# 40-PRE_REG_AND_SERDES_POWER_SUPPLY.net
KiCad netlist of a schematic drawn in Altium Designer
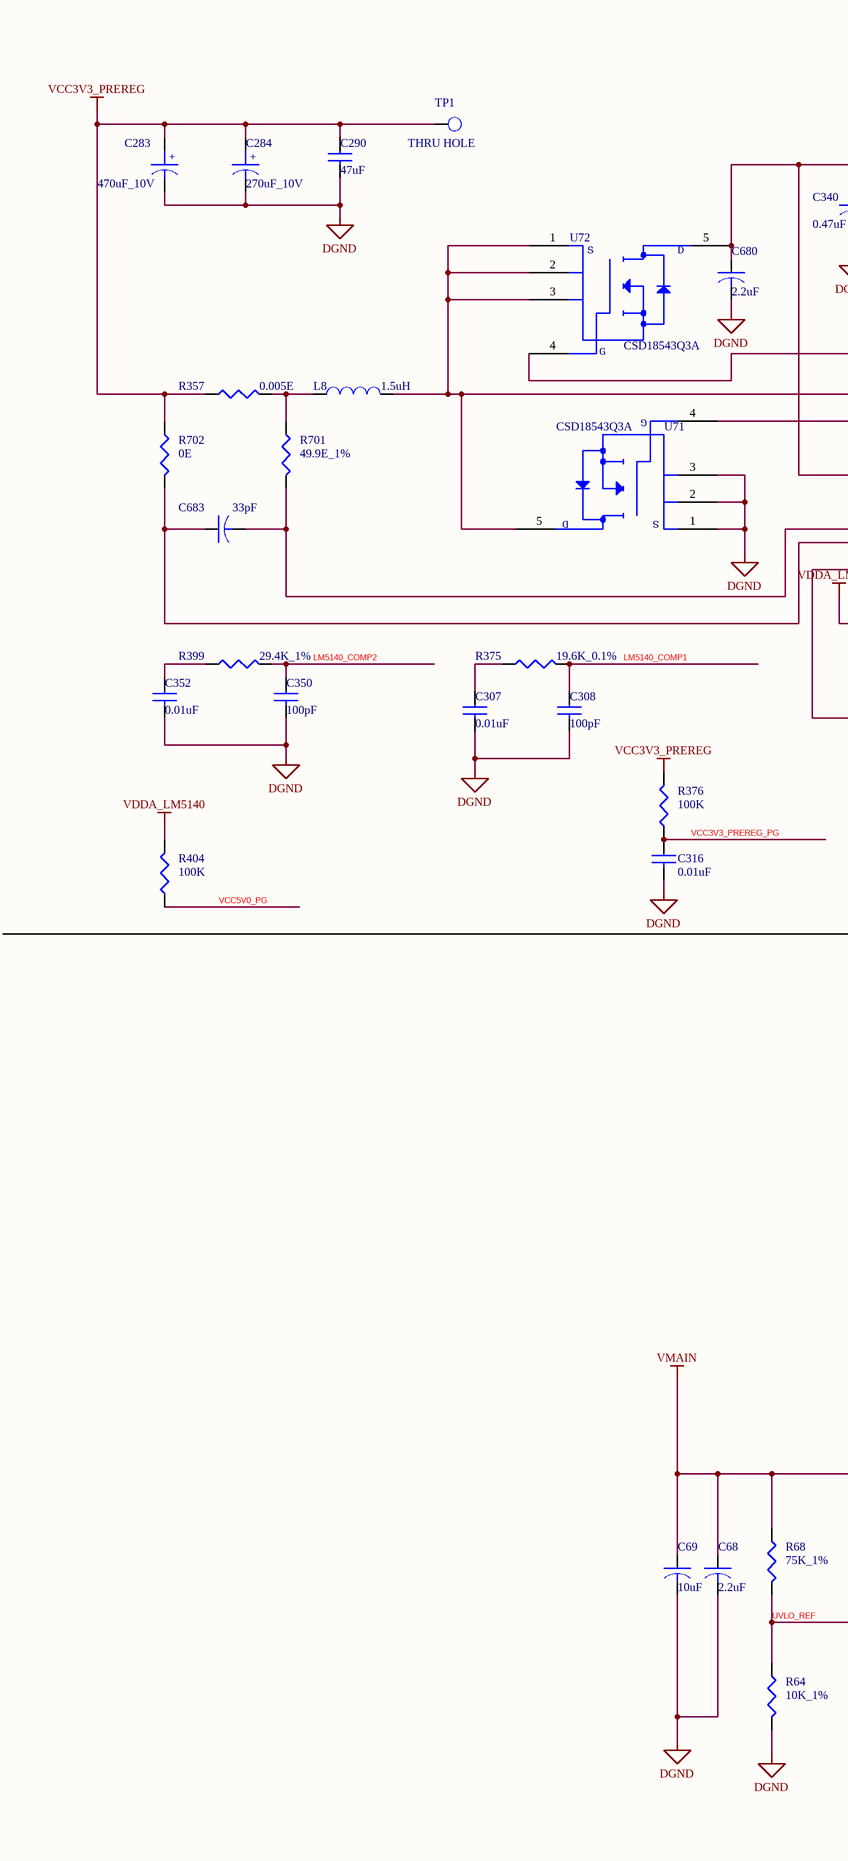
[diagram p0: 40-PRE_REG AND SERDES POWER SUPPLY.SchDoc, left]
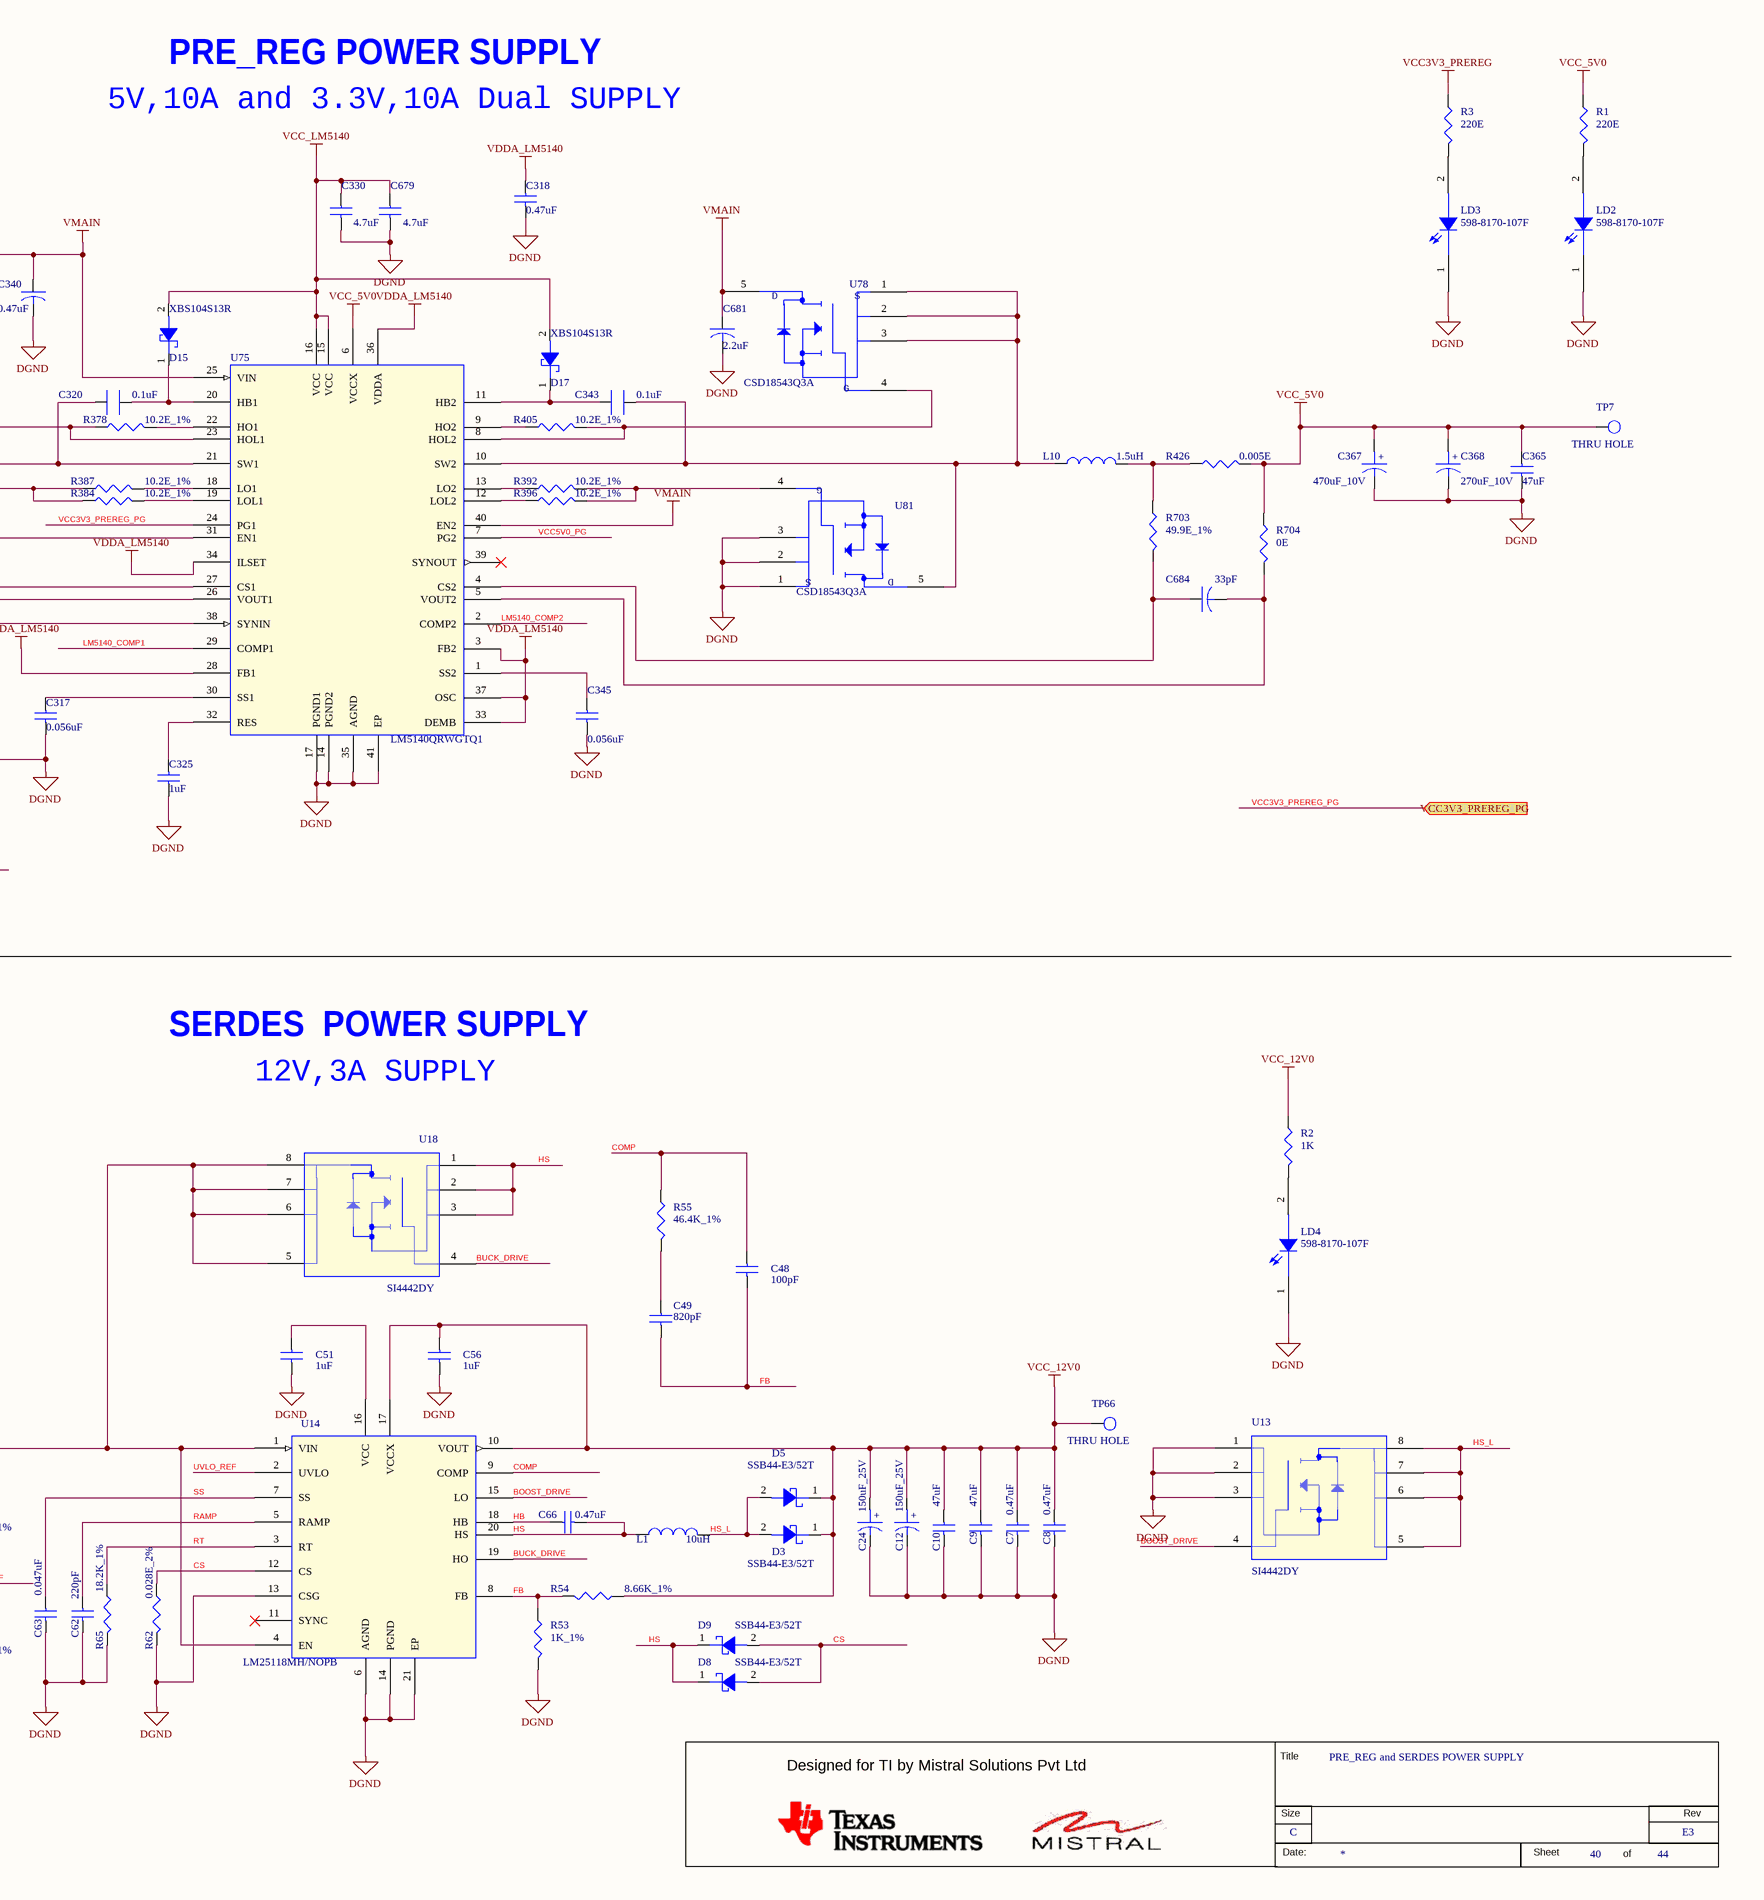
[diagram p1: 40-PRE_REG AND SERDES POWER SUPPLY.SchDoc, right]

(export (version "E")
  (design (tool "Eeschema 10.0.6"))
  (components
    (comp (ref "C7")
      (value "0.47uF")
      (footprint "CAP0805_1")
      (description "CAP CERAMIC 0.47uF 25V 10% X5R 0805")
      (fields (field (name "DISTRIBUTOR_PART_NUMBER") "587-1290-1-ND") (field (name "VOLTAGE") "25V"))
      (libsource (lib "*") (part "CAP_Dup5"))
    )
    (comp (ref "C8")
      (value "0.47uF")
      (footprint "CAP0805_1")
      (description "CAP CERAMIC 0.47uF 25V 10% X5R 0805")
      (fields (field (name "DISTRIBUTOR_PART_NUMBER") "587-1290-1-ND") (field (name "VOLTAGE") "25V"))
      (libsource (lib "*") (part "CAP_Dup5"))
    )
    (comp (ref "C9")
      (value "47uF")
      (footprint "CAP1206_2")
      (description "CAP CERAMIC 47uF 25V 20% X5R 1206")
      (fields (field (name "DISTRIBUTOR_PART_NUMBER") "490-16268-1-ND") (field (name "VOLTAGE") "25V"))
      (libsource (lib "*") (part "CAP_Dup5"))
    )
    (comp (ref "C10")
      (value "47uF")
      (footprint "CAP1206_2")
      (description "CAP CERAMIC 47uF 25V 20% X5R 1206")
      (fields
        (field (name "MISTRAL PART NO") "120013050002-R")
        (field (name "MFR_PART_NUMBER") "GRM31CR61E476ME44L")
      )
      (libsource (lib "*") (part "CAP_Dup5"))
    )
    (comp (ref "C12")
      (value "150uF_25V")
      (footprint "CAPAE_CASE8383_11")
      (description "CAP ELECTROLYTIC 150uF 25V 20% CASE_8383")
      (fields
        (field (name "MISTRAL PART NO") "120018010023-R")
        (field (name "MFR_PART_NUMBER") "UWT1E151MNL1GS")
      )
      (libsource (lib "*") (part "CAP_POL"))
    )
    (comp (ref "C24")
      (value "150uF_25V")
      (footprint "CAPAE_CASE8383_11")
      (description "CAP ELECTROLYTIC 150uF 25V 20% CASE_8383")
      (fields
        (field (name "MISTRAL PART NO") "120018010023-R")
        (field (name "MFR_PART_NUMBER") "UWT1E151MNL1GS")
      )
      (libsource (lib "*") (part "CAP_POL"))
    )
    (comp (ref "C48")
      (value "100pF")
      (footprint "CAP0402")
      (description "CAP CERAMIC 100pF 50V 10% X7R 0402")
      (fields (field (name "DISTRIBUTOR_PART_NUMBER") "311-1419-1-ND") (field (name "VOLTAGE") "50V"))
      (libsource (lib "*") (part "CAP_Dup5"))
    )
    (comp (ref "C49")
      (value "820pF")
      (footprint "CAP0402_0-75")
      (description "CAP CERAMIC 820pF 50V 5% C0G(NP0) 0402")
      (fields (field (name "DISTRIBUTOR_PART_NUMBER") "445-13812-1-ND") (field (name "VOLTAGE") "50V"))
      (libsource (lib "*") (part "CAP_Dup5"))
    )
    (comp (ref "C51")
      (value "1uF")
      (footprint "CAP0603_1")
      (description "CAP CERAMIC 1uF 25V 10% X5R 0603")
      (fields
        (field (name "MISTRAL PART NO") "120010080040-R")
        (field (name "MFR_PART_NUMBER") "06033D105KAT2A")
      )
      (libsource (lib "*") (part "CAP_Dup5"))
    )
    (comp (ref "C56")
      (value "1uF")
      (footprint "CAP0603_1")
      (description "CAP CERAMIC 1uF 25V 10% X5R 0603")
      (fields
        (field (name "MISTRAL PART NO") "120010080040-R")
        (field (name "MFR_PART_NUMBER") "06033D105KAT2A")
      )
      (libsource (lib "*") (part "CAP_Dup5"))
    )
    (comp (ref "C62")
      (value "220pF")
      (footprint "CAP0402")
      (description "CAP CERAMIC 220pF 25V 5% C0G 0402")
      (fields
        (field (name "MISTRAL PART NO") "120015120016-R")
        (field (name "MFR_PART_NUMBER") "GRM1555C1E221JA01D")
      )
      (libsource (lib "*") (part "CAP_Dup5"))
    )
    (comp (ref "C63")
      (value "0.047uF")
      (footprint "CAP0402_0-75")
      (description "CAP CERAMIC 0.047uF 50V 10% X7R 0402")
      (fields (field (name "DISTRIBUTOR_PART_NUMBER") "GRM155R71H473KE14J-ND") (field (name "VOLTAGE") "50V"))
      (libsource (lib "*") (part "CAP_Dup5"))
    )
    (comp (ref "C66")
      (value "0.47uF")
      (footprint "CAP0805_1")
      (description "CAP CERAMIC 0.47uF 25V 10% X5R 0805")
      (fields (field (name "DISTRIBUTOR_PART_NUMBER") "587-1290-1-ND") (field (name "VOLTAGE") "25V"))
      (libsource (lib "*") (part "CAP_Dup5"))
    )
    (comp (ref "C68")
      (value "2.2uF")
      (footprint "CAP0805_1")
      (description "CAP CERAMIC 2.2uF 50V 10% X5R 0805")
      (fields
        (field (name "MISTRAL PART NO") "120018010012-R")
        (field (name "MFR_PART_NUMBER") "C2012X5R1H225K085AB")
      )
      (libsource (lib "*") (part "CAP"))
    )
    (comp (ref "C69")
      (value "10uF")
      (footprint "CAP1206_2")
      (description "CAP CERAMIC 10uF 50V 20% X5R 1206")
      (fields
        (field (name "MISTRAL PART NO") "120018010013-R")
        (field (name "MFR_PART_NUMBER") "GRM31CR61H106MA12L")
      )
      (libsource (lib "*") (part "CAP"))
    )
    (comp (ref "C283")
      (value "470uF_10V")
      (footprint "CAPAE_D8CASE_8")
      (description "CAP ELECTROLYTIC 470uF 10V 20% D8CASE_6666")
      (fields (field (name "DISTRIBUTOR_PART_NUMBER") "P15094CT-ND") (field (name "VOLTAGE") "10V"))
      (libsource (lib "*") (part "CAP_POL"))
    )
    (comp (ref "C284")
      (value "270uF_10V")
      (footprint "CAP_87510524_270X270_SMD_7-7")
      (description "CAP POLMER 270uF 10V 20% SMD")
      (fields
        (field (name "MISTRAL PART NO") "120018010024-R")
        (field (name "MFR_PART_NUMBER") "875105245014")
      )
      (libsource (lib "*") (part "CAP_POL"))
    )
    (comp (ref "C290")
      (value "47uF")
      (footprint "CAP1206_2")
      (description "CAP CERAMIC 47uF 25V 20% X5R 1206")
      (fields
        (field (name "MISTRAL PART NO") "120013050002-R")
        (field (name "MFR_PART_NUMBER") "GRM31CR61E476ME44L")
      )
      (libsource (lib "*") (part "CAP_Dup5"))
    )
    (comp (ref "C307")
      (value "0.01uF")
      (footprint "CAP0402_0-75")
      (description "CAP CERAMIC 0.01uF 10V 10% X7R 0402")
      (fields
        (field (name "MISTRAL PART NO") "120009030017-R")
        (field (name "MFR_PART_NUMBER") "0402ZC103KAT2A")
      )
      (libsource (lib "*") (part "CAP_Dup5"))
    )
    (comp (ref "C308")
      (value "100pF")
      (footprint "CAP0402")
      (description "CAP CERAMIC 100pF 50V 10% X7R 0402")
      (fields
        (field (name "MISTRAL PART NO") "120014030006-R")
        (field (name "MFR_PART_NUMBER") "CC0402KRX7R9BB101")
      )
      (libsource (lib "*") (part "CAP_Dup5"))
    )
    (comp (ref "C316")
      (value "0.01uF")
      (footprint "CAP0201_0-5")
      (description "CAP CERAMIC 0.01uF 25V 10% X5R 0201")
      (fields (field (name "DISTRIBUTOR_PART_NUMBER") "GRM033R61E103KA12J-ND") (field (name "VOLTAGE") "25V"))
      (libsource (lib "*") (part "CAP_Dup5"))
    )
    (comp (ref "C317")
      (value "0.056uF")
      (footprint "CAP0402_0-75")
      (description "CAP CERAMIC 0.056uF 10V 10% X5R 0402")
      (fields (field (name "DISTRIBUTOR_PART_NUMBER") "490-5413-1-ND") (field (name "VOLTAGE") "10V"))
      (libsource (lib "*") (part "CAP_Dup5"))
    )
    (comp (ref "C318")
      (value "0.47uF")
      (footprint "CAP0603_1")
      (description "CAP CERAMIC 0.47uF 25V 10% X7R 0603")
      (fields
        (field (name "MISTRAL PART NO") "120009030111-R")
        (field (name "MFR_PART_NUMBER") "CC0603KRX7R8BB474")
      )
      (libsource (lib "*") (part "CAP_Dup5"))
    )
    (comp (ref "C320")
      (value "0.1uF")
      (footprint "TMDX654GPEVM_BRD:CAP0201_0-5")
      (description "CAP CERAMIC 0.1uF 16V 10% X5R 0201")
      (fields
        (field (name "MISTRAL PART NO") "120009030072-R")
        (field (name "MFR_PART_NUMBER") "GRM033R61C104KE84J")
      )
      (libsource (lib "*") (part "CAP_Dup3"))
    )
    (comp (ref "C325")
      (value "1uF")
      (footprint "CAP0402_0-75")
      (description "CAP CERAMIC 1uF 16V 20% X5R 0402")
      (fields
        (field (name "MISTRAL PART NO") "120018020006-R")
        (field (name "MFR_PART_NUMBER") "EMK105BJ105MV-F")
      )
      (libsource (lib "*") (part "CAP_Dup5"))
    )
    (comp (ref "C330")
      (value "4.7uF")
      (footprint "CAP0402_0-75")
      (description "CAP CERAMIC 4.7uF 10V 20% X5R 0402")
      (fields (field (name "DISTRIBUTOR_PART_NUMBER") "478-10791-1-ND") (field (name "VOLTAGE") "10V"))
      (libsource (lib "*") (part "CAP_Dup5"))
    )
    (comp (ref "C340")
      (value "0.47uF")
      (footprint "CAP0805_1-5")
      (description "CAP CERAMIC 0.47uF 50V 5% X7R 0805")
      (fields
        (field (name "MISTRAL PART NO") "120018010019-R")
        (field (name "MFR_PART_NUMBER") "CC0805JKX7R9BB474")
      )
      (libsource (lib "*") (part "CAP"))
    )
    (comp (ref "C343")
      (value "0.1uF")
      (footprint "TMDX654GPEVM_BRD:CAP0201_0-5")
      (description "CAP CERAMIC 0.1uF 16V 10% X5R 0201")
      (fields (field (name "DISTRIBUTOR_PART_NUMBER") "490-16742-1-ND") (field (name "VOLTAGE") "16V"))
      (libsource (lib "*") (part "CAP_Dup3"))
    )
    (comp (ref "C345")
      (value "0.056uF")
      (footprint "CAP0402_0-75")
      (description "CAP CERAMIC 0.056uF 10V 10% X5R 0402")
      (fields
        (field (name "MISTRAL PART NO") "120018010014-R")
        (field (name "MFR_PART_NUMBER") "GRM155R61A563KA01D")
      )
      (libsource (lib "*") (part "CAP_Dup5"))
    )
    (comp (ref "C350")
      (value "100pF")
      (footprint "CAP0402")
      (description "CAP CERAMIC 100pF 50V 10% X7R 0402")
      (fields (field (name "DISTRIBUTOR_PART_NUMBER") "311-1419-1-ND") (field (name "VOLTAGE") "50V"))
      (libsource (lib "*") (part "CAP_Dup5"))
    )
    (comp (ref "C352")
      (value "0.01uF")
      (footprint "CAP0402_0-75")
      (description "CAP CERAMIC 0.01uF 10V 10% X7R 0402")
      (fields
        (field (name "MISTRAL PART NO") "120009030017-R")
        (field (name "MFR_PART_NUMBER") "0402ZC103KAT2A")
      )
      (libsource (lib "*") (part "CAP_Dup5"))
    )
    (comp (ref "C365")
      (value "47uF")
      (footprint "CAP1206_2")
      (description "CAP CERAMIC 47uF 25V 20% X5R 1206")
      (fields
        (field (name "MISTRAL PART NO") "120013050002-R")
        (field (name "MFR_PART_NUMBER") "GRM31CR61E476ME44L")
      )
      (libsource (lib "*") (part "CAP_Dup5"))
    )
    (comp (ref "C367")
      (value "470uF_10V")
      (footprint "CAPAE_D8CASE_8")
      (description "CAP ELECTROLYTIC 470uF 10V 20% D8CASE_6666")
      (fields (field (name "DISTRIBUTOR_PART_NUMBER") "P15094CT-ND") (field (name "VOLTAGE") "10V"))
      (libsource (lib "*") (part "CAP_POL"))
    )
    (comp (ref "C368")
      (value "270uF_10V")
      (footprint "CAP_87510524_270X270_SMD_7-7")
      (description "CAP POLMER 270uF 10V 20% SMD")
      (fields (field (name "DISTRIBUTOR_PART_NUMBER") "732-6414-1-ND") (field (name "VOLTAGE") "10V"))
      (libsource (lib "*") (part "CAP_POL"))
    )
    (comp (ref "C679")
      (value "4.7uF")
      (footprint "CAP0402_0-75")
      (description "CAP CERAMIC 4.7uF 10V 20% X5R 0402")
      (fields
        (field (name "MISTRAL PART NO") "120012060002-R")
        (field (name "MFR_PART_NUMBER") "0402ZD475MAT2A")
      )
      (libsource (lib "*") (part "CAP_Dup5"))
    )
    (comp (ref "C680")
      (value "2.2uF")
      (footprint "CAP0805_1")
      (description "CAP CERAMIC 2.2uF 50V 10% X5R 0805")
      (fields (field (name "DISTRIBUTOR_PART_NUMBER") "445-14407-1-ND") (field (name "VOLTAGE") "50V"))
      (libsource (lib "*") (part "CAP"))
    )
    (comp (ref "C681")
      (value "2.2uF")
      (footprint "CAP0805_1")
      (description "CAP CERAMIC 2.2uF 50V 10% X5R 0805")
      (fields (field (name "DISTRIBUTOR_PART_NUMBER") "445-14407-1-ND") (field (name "VOLTAGE") "50V"))
      (libsource (lib "*") (part "CAP"))
    )
    (comp (ref "C683")
      (value "33pF")
      (footprint "CAP0201_0-5")
      (description "CAP CERAMIC 33pF 50V 2% C0G(NP0) 0201")
      (fields
        (field (name "MISTRAL PART NO") "120018010015-R")
        (field (name "MFR_PART_NUMBER") "GRM0335C1H330GA01D")
      )
      (libsource (lib "*") (part "CAP"))
    )
    (comp (ref "C684")
      (value "33pF")
      (footprint "CAP0201_0-5")
      (description "CAP CERAMIC 33pF 50V 2% C0G(NP0) 0201")
      (fields (field (name "DISTRIBUTOR_PART_NUMBER") "490-11325-1-ND") (field (name "VOLTAGE") "50V"))
      (libsource (lib "*") (part "CAP"))
    )
    (comp (ref "D3")
      (value "SSB44-E3/52T")
      (footprint "DIO_SMB_2-5")
      (description "DIODE SCHOTTKY RECTIFIER 40V 4A DO-214AA(SMB)")
      (fields (field (name "DISTRIBUTOR_PART_NUMBER") "SSB44-E3/52TGICT-ND") (field (name "VOLTAGE") "NA"))
      (libsource (lib "*") (part "DIODE_SCHOTTKY"))
    )
    (comp (ref "D5")
      (value "SSB44-E3/52T")
      (footprint "DIO_SMB_2-5")
      (description "DIODE SCHOTTKY RECTIFIER 40V 4A DO-214AA(SMB)")
      (fields (field (name "MISTRAL PART NO") "130017100021-R") (field (name "TOLERANCE") "NA"))
      (libsource (lib "*") (part "DIODE_SCHOTTKY"))
    )
    (comp (ref "D8")
      (value "SSB44-E3/52T")
      (footprint "DIO_SMB_2-5")
      (description "DIODE SCHOTTKY RECTIFIER 40V 4A DO-214AA(SMB)")
      (fields (field (name "MISTRAL PART NO") "130017100021-R") (field (name "TOLERANCE") "NA"))
      (libsource (lib "*") (part "DIODE_SCHOTTKY"))
    )
    (comp (ref "D9")
      (value "SSB44-E3/52T")
      (footprint "DIO_SMB_2-5")
      (description "DIODE SCHOTTKY RECTIFIER 40V 4A DO-214AA(SMB)")
      (fields (field (name "MISTRAL PART NO") "130017100021-R") (field (name "TOLERANCE") "NA"))
      (libsource (lib "*") (part "DIODE_SCHOTTKY"))
    )
    (comp (ref "D15")
      (value "XBS104S13R")
      (footprint "DIO_SOD323_1")
      (description "DIODE SCHOTTKY 40V 1A SOD323A")
      (fields (field (name "DISTRIBUTOR_PART_NUMBER") "893-1188-1-ND") (field (name "VOLTAGE") "40V"))
      (libsource (lib "*") (part "DIODE_SCHOTTKY"))
    )
    (comp (ref "D17")
      (value "XBS104S13R")
      (footprint "DIO_SOD323_1")
      (description "DIODE SCHOTTKY 40V 1A SOD323A")
      (fields
        (field (name "MISTRAL PART NO") "130018020038-R")
        (field (name "MFR_PART_NUMBER") "XBS104S13R-G")
      )
      (libsource (lib "*") (part "DIODE_SCHOTTKY"))
    )
    (comp (ref "L1")
      (value "10uH")
      (footprint "IND_ETQP5MYFM_310X290_SMD_5-4")
      (description "IND POWER 10uH 5.7A 20% SMD")
      (fields (field (name "VOLTAGE") "NA") (field (name "DISTRIBUTOR_PART_NUMBER") "P17067CT-ND"))
      (libsource (lib "*") (part "INDUCTOR"))
    )
    (comp (ref "L8")
      (value "1.5uH")
      (footprint "IND_ETQP4MKVK_350X330_SMD_4")
      (description "IND POWER 1.5uH 15.1A 20% SMD")
      (fields
        (field (name "MISTRAL PART NO") "130017100018-R")
        (field (name "MFR_PART_NUMBER") "ETQ-P4M1R5KVK")
      )
      (libsource (lib "*") (part "INDUCTOR"))
    )
    (comp (ref "L10")
      (value "1.5uH")
      (footprint "IND_ETQP4MKVK_350X330_SMD_4")
      (description "IND POWER 1.5uH 15.1A 20% SMD")
      (fields (field (name "DISTRIBUTOR_PART_NUMBER") "PCD2466CT-ND") (field (name "VOLTAGE") "NA"))
      (libsource (lib "*") (part "INDUCTOR"))
    )
    (comp (ref "LD2")
      (value "598-8170-107F")
      (footprint "LED_0805_0-7")
      (description "LED ALINGAP GREEN CLEAR 0805")
      (fields (field (name "DISTRIBUTOR_PART_NUMBER") "350-2044-1-ND") (field (name "VOLTAGE") "NA"))
      (libsource (lib "*") (part "LED_598-8170-107F"))
    )
    (comp (ref "LD3")
      (value "598-8170-107F")
      (footprint "LED_0805_0-7")
      (description "LED ALINGAP GREEN CLEAR 0805")
      (fields (field (name "DISTRIBUTOR_PART_NUMBER") "350-2044-1-ND") (field (name "VOLTAGE") "NA"))
      (libsource (lib "*") (part "LED_598-8170-107F"))
    )
    (comp (ref "LD4")
      (value "598-8170-107F")
      (footprint "LED_0805_0-7")
      (description "LED ALINGAP GREEN CLEAR 0805")
      (fields (field (name "DISTRIBUTOR_PART_NUMBER") "350-2044-1-ND") (field (name "VOLTAGE") "NA"))
      (libsource (lib "*") (part "LED_598-8170-107F"))
    )
    (comp (ref "R1")
      (value "220E")
      (footprint "RES0402_0-5")
      (description "RES 220E 1/16W 5% 0402")
      (fields (field (name "VOLTAGE") "NA") (field (name "DISTRIBUTOR_PART_NUMBER") "P220JCT-ND"))
      (libsource (lib "*") (part "RESISTOR_Dup5"))
    )
    (comp (ref "R2")
      (value "1K")
      (footprint "RES0201")
      (description "RES 1K 1/20W 5% 0201")
      (fields
        (field (name "MISTRAL PART NO") "110015080014-R")
        (field (name "MFR_PART_NUMBER") "CRCW02011K00FKED")
      )
      (libsource (lib "*") (part "RESISTOR_Dup5"))
    )
    (comp (ref "R3")
      (value "220E")
      (footprint "RES0402_0-5")
      (description "RES 220E 1/16W 5% 0402")
      (fields (field (name "VOLTAGE") "NA") (field (name "DISTRIBUTOR_PART_NUMBER") "P220JCT-ND"))
      (libsource (lib "*") (part "RESISTOR_Dup5"))
    )
    (comp (ref "R53")
      (value "1K_1%")
      (footprint "RES0402_0-5")
      (description "RES 1K 1/10W 1% 0402")
      (fields
        (field (name "MISTRAL PART NO") "110009030411-R")
        (field (name "MFR_PART_NUMBER") "ERJ-2RKF1001X")
      )
      (libsource (lib "*") (part "RESISTOR_Dup5"))
    )
    (comp (ref "R54")
      (value "8.66K_1%")
      (footprint "RES0402")
      (description "RES 8.66K 1/10W 1% 0402")
      (fields
        (field (name "MISTRAL PART NO") "110012090010-R")
        (field (name "MFR_PART_NUMBER") "ERJ-2RKF8661X")
      )
      (libsource (lib "*") (part "RESISTOR_Dup5"))
    )
    (comp (ref "R55")
      (value "46.4K_1%")
      (footprint "RES0402")
      (description "RES 46.4K 1/16W 1% 0402")
      (fields (field (name "DISTRIBUTOR_PART_NUMBER") "541-46.4KLCT-ND") (field (name "VOLTAGE") "NA"))
      (libsource (lib "*") (part "RESISTOR_Dup5"))
    )
    (comp (ref "R62")
      (value "0.028E_2%")
      (footprint "RES0815_0-75")
      (description "RES 0.028E 1W 2% 1508")
      (fields
        (field (name "MISTRAL PART NO") "110017090012-R")
        (field (name "MFR_PART_NUMBER") "RL3720WT-R028-G")
      )
      (libsource (lib "*") (part "RESISTOR_Dup5"))
    )
    (comp (ref "R64")
      (value "10K_1%")
      (footprint "RES0402_0-5")
      (description "RES 10K 1/16W 1% 0402")
      (fields (field (name "DISTRIBUTOR_PART_NUMBER") "311-10.0KLRTR-ND") (field (name "VOLTAGE") "NA"))
      (libsource (lib "*") (part "RESISTOR_Dup5"))
    )
    (comp (ref "R65")
      (value "18.2K_1%")
      (footprint "RES0402")
      (description "RES 18.2K 1/16W 1% 0402")
      (fields
        (field (name "MISTRAL PART NO") "110009031211-R")
        (field (name "MFR_PART_NUMBER") "ERJ-2RKF1822X")
      )
      (libsource (lib "*") (part "RESISTOR_Dup5"))
    )
    (comp (ref "R68")
      (value "75K_1%")
      (footprint "RES0402_0-5")
      (description "RES 75K 1/10W 1% 0402")
      (fields (field (name "VOLTAGE") "NA") (field (name "DISTRIBUTOR_PART_NUMBER") "P75.0KLCT-ND"))
      (libsource (lib "*") (part "RESISTOR_Dup5"))
    )
    (comp (ref "R357")
      (value "0.005E")
      (footprint "RES1206")
      (description "RES 0.005E 1/2W 1% 1206")
      (fields
        (field (name "MISTRAL PART NO") "110009030043-P")
        (field (name "MFR_PART_NUMBER") "WSL12065L000FEA18")
      )
      (libsource (lib "*") (part "RESISTOR_Dup5"))
    )
    (comp (ref "R375")
      (value "19.6K_0.1%")
      (footprint "RES0402")
      (description "RES 19.6K 1/16W 0.1% 0402")
      (fields
        (field (name "MISTRAL PART NO") "110011100020-R")
        (field (name "MFR_PART_NUMBER") "TNPW040219K6BEED")
      )
      (libsource (lib "*") (part "RESISTOR_Dup5"))
    )
    (comp (ref "R376")
      (value "100K")
      (footprint "RES0402_0-5")
      (description "RES 100K 1/16W 5% 0402")
      (fields
        (field (name "MISTRAL PART NO") "110011060002-R")
        (field (name "MFR_PART_NUMBER") "CRCW0402100KJNED")
      )
      (libsource (lib "*") (part "RESISTOR_Dup5"))
    )
    (comp (ref "R378")
      (value "10.2E_1%")
      (footprint "RES0402_0-5")
      (description "RES 10.2E 1/16W 1% 0402")
      (fields (field (name "DISTRIBUTOR_PART_NUMBER") "541-10.2LCT-ND") (field (name "VOLTAGE") "NA"))
      (libsource (lib "*") (part "RESISTOR_Dup5"))
    )
    (comp (ref "R384")
      (value "10.2E_1%")
      (footprint "RES0402_0-5")
      (description "RES 10.2E 1/16W 1% 0402")
      (fields
        (field (name "MISTRAL PART NO") "110017080001-R")
        (field (name "MFR_PART_NUMBER") "CRCW040210R2FKED")
      )
      (libsource (lib "*") (part "RESISTOR_Dup5"))
    )
    (comp (ref "R387")
      (value "10.2E_1%")
      (footprint "RES0402_0-5")
      (description "RES 10.2E 1/16W 1% 0402")
      (fields (field (name "DISTRIBUTOR_PART_NUMBER") "541-10.2LCT-ND") (field (name "VOLTAGE") "NA"))
      (libsource (lib "*") (part "RESISTOR_Dup5"))
    )
    (comp (ref "R392")
      (value "10.2E_1%")
      (footprint "RES0402_0-5")
      (description "RES 10.2E 1/16W 1% 0402")
      (fields
        (field (name "MISTRAL PART NO") "110017080001-R")
        (field (name "MFR_PART_NUMBER") "CRCW040210R2FKED")
      )
      (libsource (lib "*") (part "RESISTOR_Dup5"))
    )
    (comp (ref "R396")
      (value "10.2E_1%")
      (footprint "RES0402_0-5")
      (description "RES 10.2E 1/16W 1% 0402")
      (fields (field (name "DISTRIBUTOR_PART_NUMBER") "541-10.2LCT-ND") (field (name "VOLTAGE") "NA"))
      (libsource (lib "*") (part "RESISTOR_Dup5"))
    )
    (comp (ref "R399")
      (value "29.4K_1%")
      (footprint "RES0402")
      (description "RES 29.4K 1/16W 1% 0402")
      (fields (field (name "DISTRIBUTOR_PART_NUMBER") "P29.4KLTR-ND") (field (name "TOLERANCE") "1%"))
      (libsource (lib "*") (part "RESISTOR_Dup5"))
    )
    (comp (ref "R404")
      (value "100K")
      (footprint "RES0402_0-5")
      (description "RES 100K 1/16W 5% 0402")
      (fields (field (name "DISTRIBUTOR_PART_NUMBER") "541-100KJCT-ND") (field (name "VOLTAGE") "NA"))
      (libsource (lib "*") (part "RESISTOR_Dup5"))
    )
    (comp (ref "R405")
      (value "10.2E_1%")
      (footprint "RES0402_0-5")
      (description "RES 10.2E 1/16W 1% 0402")
      (fields (field (name "DISTRIBUTOR_PART_NUMBER") "541-10.2LCT-ND") (field (name "VOLTAGE") "NA"))
      (libsource (lib "*") (part "RESISTOR_Dup5"))
    )
    (comp (ref "R426")
      (value "0.005E")
      (footprint "RES1206")
      (description "RES 0.005E 1/2W 1% 1206")
      (fields
        (field (name "MISTRAL PART NO") "110009030043-P")
        (field (name "MFR_PART_NUMBER") "WSL12065L000FEA18")
      )
      (libsource (lib "*") (part "RESISTOR_Dup5"))
    )
    (comp (ref "R701")
      (value "49.9E_1%")
      (footprint "RES0201")
      (description "RES 49.9E 1/20W 1% 0201")
      (fields
        (field (name "MISTRAL PART NO") "110009030893-R")
        (field (name "MFR_PART_NUMBER") "ERJ-1GEF49R9C")
      )
      (libsource (lib "*") (part "RESISTOR"))
    )
    (comp (ref "R702")
      (value "0E")
      (footprint "RES0402_0-5")
      (description "RES 0E 1/16W 0402")
      (fields
        (field (name "MISTRAL PART NO") "110010080019-P")
        (field (name "MFR_PART_NUMBER") "CRCW04020000Z0ED")
      )
      (libsource (lib "*") (part "RESISTOR"))
    )
    (comp (ref "R703")
      (value "49.9E_1%")
      (footprint "RES0201")
      (description "RES 49.9E 1/20W 1% 0201")
      (fields (field (name "DISTRIBUTOR_PART_NUMBER") "P49.9ABCT-ND") (field (name "TOLERANCE") "1%"))
      (libsource (lib "*") (part "RESISTOR"))
    )
    (comp (ref "R704")
      (value "0E")
      (footprint "RES0402_0-5")
      (description "RES 0E 1/16W 0402")
      (fields
        (field (name "MISTRAL PART NO") "110010080019-P")
        (field (name "MFR_PART_NUMBER") "CRCW04020000Z0ED")
      )
      (libsource (lib "*") (part "RESISTOR"))
    )
    (comp (ref "TP1")
      (value "THRU HOLE")
      (footprint "TP_40X65")
      (description "TESTPOINT 1.0MM DRILL PTH")
      (fields (field (name "DISTRIBUTOR_PART_NUMBER") "NA") (field (name "MFR_PART_NUMBER") "TP_40X65"))
      (libsource (lib "*") (part "TESTPOINT"))
    )
    (comp (ref "TP7")
      (value "THRU HOLE")
      (footprint "TP_40X65")
      (description "TESTPOINT 1.0MM DRILL PTH")
      (fields (field (name "MISTRAL PART NO") "130009030938") (field (name "MFR_PART_NUMBER") "TP_40X65"))
      (libsource (lib "*") (part "TESTPOINT"))
    )
    (comp (ref "TP66")
      (value "THRU HOLE")
      (footprint "TP_40X65")
      (description "TESTPOINT 1.0MM DRILL PTH")
      (fields (field (name "DISTRIBUTOR_PART_NUMBER") "NA") (field (name "MFR_PART_NUMBER") "TP_40X65"))
      (libsource (lib "*") (part "TESTPOINT"))
    )
    (comp (ref "U13")
      (value "SI4442DY")
      (footprint "SOIC8_1-8")
      (description "IC MOSFET N-CHANNEL 30V 15A SOIC8")
      (fields (field (name "DISTRIBUTOR_PART_NUMBER") "781-SI4442DY") (field (name "VOLTAGE") "NA"))
      (libsource (lib "*") (part "MOSFET_SI4442DY"))
    )
    (comp (ref "U14")
      (value "LM25118MH/NOPB")
      (footprint "ETSSOP20_25-59_260X180_1-1")
      (description "IC WIDE VOLTAGE BUCK BOOST CONTROLLER HTSSOP20")
      (fields (field (name "MISTRAL PART NO") "142017090017-R") (field (name "TOLERANCE") "NA"))
      (libsource (lib "*") (part "LM25118MH_HTSSOP20"))
    )
    (comp (ref "U18")
      (value "SI4442DY")
      (footprint "SOIC8_1-8")
      (description "IC MOSFET N-CHANNEL 30V 15A SOIC8")
      (fields (field (name "DISTRIBUTOR_PART_NUMBER") "781-SI4442DY") (field (name "VOLTAGE") "NA"))
      (libsource (lib "*") (part "MOSFET_SI4442DY"))
    )
    (comp (ref "U71")
      (value "CSD18543Q3A")
      (footprint "VSONP8_CSD18543Q_120X130_0-9")
      (description "IC MOSFET N-CHANNEL 60V VSONP8")
      (fields (field (name "DISTRIBUTOR_PART_NUMBER") "296-47321-1-ND") (field (name "VOLTAGE") "60V"))
      (libsource (lib "*") (part "MOSFET_CSD18501Q5A"))
    )
    (comp (ref "U72")
      (value "CSD18543Q3A")
      (footprint "VSONP8_CSD18543Q_120X130_0-9")
      (description "IC MOSFET N-CHANNEL 60V VSONP8")
      (fields (field (name "DISTRIBUTOR_PART_NUMBER") "296-47321-1-ND") (field (name "VOLTAGE") "60V"))
      (libsource (lib "*") (part "MOSFET_CSD18501Q5A"))
    )
    (comp (ref "U75")
      (value "LM5140QRWGTQ1")
      (footprint "TMDX654GPEVM_BRD:QFN40_19-68_240X240_0-9")
      (description "IC WIDE I/P DUAL SYNCHRONOUS BUCK CONTROLLER VQFNP40")
      (fields (field (name "MISTRAL PART NO") "142017100003-R") (field (name "TOLERANCE") "NA"))
      (libsource (lib "*") (part "LM5140QRWGTQ1_VQFNP40"))
    )
    (comp (ref "U78")
      (value "CSD18543Q3A")
      (footprint "VSONP8_CSD18543Q_120X130_0-9")
      (description "IC MOSFET N-CHANNEL 60V VSONP8")
      (fields (field (name "MISTRAL PART NO") "142017100004-R") (field (name "TOLERANCE") "NA"))
      (libsource (lib "*") (part "MOSFET_CSD18501Q5A"))
    )
    (comp (ref "U81")
      (value "CSD18543Q3A")
      (footprint "VSONP8_CSD18543Q_120X130_0-9")
      (description "IC MOSFET N-CHANNEL 60V VSONP8")
      (fields (field (name "DISTRIBUTOR_PART_NUMBER") "296-47321-1-ND") (field (name "VOLTAGE") "60V"))
      (libsource (lib "*") (part "MOSFET_CSD18501Q5A"))
    )
  )
  (nets
    (net (code "1") (name "/BOOST_DRIVE") (class "Default")
      (node (ref "U13") (pin "4") (pinfunction "G_4") (pintype "passive"))
      (node (ref "U14") (pin "15") (pinfunction "LO_15") (pintype "passive"))
    )
    (net (code "2") (name "/BUCK_DRIVE") (class "Default")
      (node (ref "U14") (pin "19") (pinfunction "HO_19") (pintype "passive"))
      (node (ref "U18") (pin "4") (pinfunction "G_4") (pintype "passive"))
    )
    (net (code "3") (name "/COMP") (class "Default")
      (node (ref "C48") (pin "1") (pinfunction "1_1") (pintype "passive"))
      (node (ref "R55") (pin "1") (pinfunction "1_1") (pintype "passive"))
      (node (ref "U14") (pin "9") (pinfunction "COMP_9") (pintype "passive"))
    )
    (net (code "4") (name "/CS") (class "Default")
      (node (ref "D8") (pin "2") (pinfunction "ANODE_2") (pintype "passive"))
      (node (ref "D9") (pin "2") (pinfunction "ANODE_2") (pintype "passive"))
      (node (ref "R62") (pin "1") (pinfunction "1_1") (pintype "passive"))
      (node (ref "U14") (pin "12") (pinfunction "CS_12") (pintype "passive"))
    )
    (net (code "5") (name "/FB") (class "Default")
      (node (ref "C48") (pin "2") (pinfunction "2_2") (pintype "passive"))
      (node (ref "C49") (pin "2") (pinfunction "2_2") (pintype "passive"))
      (node (ref "R53") (pin "1") (pinfunction "1_1") (pintype "passive"))
      (node (ref "R54") (pin "2") (pinfunction "2_2") (pintype "passive"))
      (node (ref "U14") (pin "8") (pinfunction "FB_8") (pintype "passive"))
    )
    (net (code "6") (name "/HB") (class "Default")
      (node (ref "C66") (pin "1") (pinfunction "1_1") (pintype "passive"))
      (node (ref "U14") (pin "18") (pinfunction "HB_18") (pintype "passive"))
    )
    (net (code "7") (name "/HS") (class "Default")
      (node (ref "C66") (pin "2") (pinfunction "2_2") (pintype "passive"))
      (node (ref "D8") (pin "1") (pinfunction "CATHODE_1") (pintype "passive"))
      (node (ref "D9") (pin "1") (pinfunction "CATHODE_1") (pintype "passive"))
      (node (ref "L1") (pin "1") (pinfunction "1_1") (pintype "passive"))
      (node (ref "U14") (pin "20") (pinfunction "HS_20") (pintype "passive"))
      (node (ref "U18") (pin "1") (pinfunction "S1_1") (pintype "passive"))
      (node (ref "U18") (pin "2") (pinfunction "S2_2") (pintype "passive"))
      (node (ref "U18") (pin "3") (pinfunction "S3_3") (pintype "passive"))
    )
    (net (code "8") (name "/HS_L") (class "Default")
      (node (ref "D3") (pin "2") (pinfunction "ANODE_2") (pintype "passive"))
      (node (ref "D5") (pin "2") (pinfunction "ANODE_2") (pintype "passive"))
      (node (ref "L1") (pin "2") (pinfunction "2_2") (pintype "passive"))
      (node (ref "U13") (pin "5") (pinfunction "D1_5") (pintype "passive"))
      (node (ref "U13") (pin "6") (pinfunction "D2_6") (pintype "passive"))
      (node (ref "U13") (pin "7") (pinfunction "D3_7") (pintype "passive"))
      (node (ref "U13") (pin "8") (pinfunction "D4_8") (pintype "passive"))
    )
    (net (code "9") (name "/LM5140_COMP1") (class "Default")
      (node (ref "C308") (pin "1") (pinfunction "1_1") (pintype "passive"))
      (node (ref "R375") (pin "2") (pinfunction "2_2") (pintype "passive"))
      (node (ref "U75") (pin "29") (pinfunction "COMP1_29") (pintype "passive"))
    )
    (net (code "10") (name "/LM5140_COMP2") (class "Default")
      (node (ref "C350") (pin "1") (pinfunction "1_1") (pintype "passive"))
      (node (ref "R399") (pin "2") (pinfunction "2_2") (pintype "passive"))
      (node (ref "U75") (pin "2") (pinfunction "COMP2_2") (pintype "passive"))
    )
    (net (code "11") (name "/RAMP") (class "Default")
      (node (ref "C62") (pin "1") (pinfunction "1_1") (pintype "passive"))
      (node (ref "U14") (pin "5") (pinfunction "RAMP_5") (pintype "passive"))
    )
    (net (code "12") (name "/RT") (class "Default")
      (node (ref "R65") (pin "1") (pinfunction "1_1") (pintype "passive"))
      (node (ref "U14") (pin "3") (pinfunction "RT_3") (pintype "passive"))
    )
    (net (code "13") (name "/SS") (class "Default")
      (node (ref "C63") (pin "1") (pinfunction "1_1") (pintype "passive"))
      (node (ref "U14") (pin "7") (pinfunction "SS_7") (pintype "passive"))
    )
    (net (code "14") (name "/UVLO_REF") (class "Default")
      (node (ref "R64") (pin "1") (pinfunction "1_1") (pintype "passive"))
      (node (ref "R68") (pin "2") (pinfunction "2_2") (pintype "passive"))
      (node (ref "U14") (pin "2") (pinfunction "UVLO_2") (pintype "passive"))
    )
    (net (code "15") (name "/VCC3V3_PREREG_PG") (class "Default")
      (node (ref "C316") (pin "1") (pinfunction "1_1") (pintype "passive"))
      (node (ref "R376") (pin "1") (pinfunction "1_1") (pintype "passive"))
      (node (ref "U75") (pin "24") (pinfunction "PG1_24") (pintype "passive"))
    )
    (net (code "16") (name "/VCC5V0_PG") (class "Default")
      (node (ref "R404") (pin "1") (pinfunction "1_1") (pintype "passive"))
      (node (ref "U75") (pin "7") (pinfunction "PG2_7") (pintype "passive"))
    )
    (net (code "17") (name "DGND") (class "Default")
      (node (ref "C10") (pin "2") (pinfunction "2_2") (pintype "passive"))
      (node (ref "C12") (pin "2") (pinfunction "2_2") (pintype "passive"))
      (node (ref "C24") (pin "2") (pinfunction "2_2") (pintype "passive"))
      (node (ref "C283") (pin "2") (pinfunction "2_2") (pintype "passive"))
      (node (ref "C284") (pin "2") (pinfunction "2_2") (pintype "passive"))
      (node (ref "C290") (pin "2") (pinfunction "2_2") (pintype "passive"))
      (node (ref "C307") (pin "2") (pinfunction "2_2") (pintype "passive"))
      (node (ref "C308") (pin "2") (pinfunction "2_2") (pintype "passive"))
      (node (ref "C316") (pin "2") (pinfunction "2_2") (pintype "passive"))
      (node (ref "C317") (pin "2") (pinfunction "2_2") (pintype "passive"))
      (node (ref "C318") (pin "2") (pinfunction "2_2") (pintype "passive"))
      (node (ref "C325") (pin "1") (pinfunction "1_1") (pintype "passive"))
      (node (ref "C330") (pin "2") (pinfunction "2_2") (pintype "passive"))
      (node (ref "C340") (pin "2") (pinfunction "2_2") (pintype "passive"))
      (node (ref "C345") (pin "2") (pinfunction "2_2") (pintype "passive"))
      (node (ref "C350") (pin "2") (pinfunction "2_2") (pintype "passive"))
      (node (ref "C352") (pin "2") (pinfunction "2_2") (pintype "passive"))
      (node (ref "C365") (pin "2") (pinfunction "2_2") (pintype "passive"))
      (node (ref "C367") (pin "2") (pinfunction "2_2") (pintype "passive"))
      (node (ref "C368") (pin "2") (pinfunction "2_2") (pintype "passive"))
      (node (ref "C51") (pin "2") (pinfunction "2_2") (pintype "passive"))
      (node (ref "C56") (pin "2") (pinfunction "2_2") (pintype "passive"))
      (node (ref "C62") (pin "2") (pinfunction "2_2") (pintype "passive"))
      (node (ref "C63") (pin "2") (pinfunction "2_2") (pintype "passive"))
      (node (ref "C679") (pin "2") (pinfunction "2_2") (pintype "passive"))
      (node (ref "C68") (pin "2") (pinfunction "2_2") (pintype "passive"))
      (node (ref "C680") (pin "2") (pinfunction "2_2") (pintype "passive"))
      (node (ref "C681") (pin "2") (pinfunction "2_2") (pintype "passive"))
      (node (ref "C69") (pin "2") (pinfunction "2_2") (pintype "passive"))
      (node (ref "C7") (pin "2") (pinfunction "2_2") (pintype "passive"))
      (node (ref "C8") (pin "2") (pinfunction "2_2") (pintype "passive"))
      (node (ref "C9") (pin "2") (pinfunction "2_2") (pintype "passive"))
      (node (ref "LD2") (pin "1") (pinfunction "1_1") (pintype "passive"))
      (node (ref "LD3") (pin "1") (pinfunction "1_1") (pintype "passive"))
      (node (ref "LD4") (pin "1") (pinfunction "1_1") (pintype "passive"))
      (node (ref "R53") (pin "2") (pinfunction "2_2") (pintype "passive"))
      (node (ref "R62") (pin "2") (pinfunction "2_2") (pintype "passive"))
      (node (ref "R64") (pin "2") (pinfunction "2_2") (pintype "passive"))
      (node (ref "R65") (pin "2") (pinfunction "2_2") (pintype "passive"))
      (node (ref "U13") (pin "1") (pinfunction "S1_1") (pintype "passive"))
      (node (ref "U13") (pin "2") (pinfunction "S2_2") (pintype "passive"))
      (node (ref "U13") (pin "3") (pinfunction "S3_3") (pintype "passive"))
      (node (ref "U14") (pin "13") (pinfunction "CSG_13") (pintype "passive"))
      (node (ref "U14") (pin "14") (pinfunction "PGND_14") (pintype "power_in"))
      (node (ref "U14") (pin "21") (pinfunction "EP_21") (pintype "power_in"))
      (node (ref "U14") (pin "6") (pinfunction "AGND_6") (pintype "power_in"))
      (node (ref "U71") (pin "1") (pinfunction "S1_1") (pintype "passive"))
      (node (ref "U71") (pin "2") (pinfunction "S2_2") (pintype "passive"))
      (node (ref "U71") (pin "3") (pinfunction "S3_3") (pintype "passive"))
      (node (ref "U75") (pin "14") (pinfunction "PGND2_14") (pintype "power_in"))
      (node (ref "U75") (pin "17") (pinfunction "PGND1_17") (pintype "power_in"))
      (node (ref "U75") (pin "35") (pinfunction "AGND_35") (pintype "power_in"))
      (node (ref "U75") (pin "38") (pinfunction "SYNIN_38") (pintype "input"))
      (node (ref "U75") (pin "41") (pinfunction "EP_41") (pintype "power_in"))
      (node (ref "U81") (pin "1") (pinfunction "S1_1") (pintype "passive"))
      (node (ref "U81") (pin "2") (pinfunction "S2_2") (pintype "passive"))
      (node (ref "U81") (pin "3") (pinfunction "S3_3") (pintype "passive"))
    )
    (net (code "18") (name "Net-(C49-Pad1)") (class "Default")
      (node (ref "C49") (pin "1") (pinfunction "1_1") (pintype "passive"))
      (node (ref "R55") (pin "2") (pinfunction "2_2") (pintype "passive"))
    )
    (net (code "19") (name "Net-(C307-Pad1)") (class "Default")
      (node (ref "C307") (pin "1") (pinfunction "1_1") (pintype "passive"))
      (node (ref "R375") (pin "1") (pinfunction "1_1") (pintype "passive"))
    )
    (net (code "20") (name "Net-(C352-Pad1)") (class "Default")
      (node (ref "C352") (pin "1") (pinfunction "1_1") (pintype "passive"))
      (node (ref "R399") (pin "1") (pinfunction "1_1") (pintype "passive"))
    )
    (net (code "21") (name "Net-(D15-CATHODE)") (class "Default")
      (node (ref "C320") (pin "1") (pinfunction "1_1") (pintype "passive"))
      (node (ref "D15") (pin "1") (pinfunction "CATHODE_1") (pintype "passive"))
      (node (ref "U75") (pin "20") (pinfunction "HB1_20") (pintype "passive"))
    )
    (net (code "22") (name "Net-(D17-CATHODE)") (class "Default")
      (node (ref "C343") (pin "2") (pinfunction "2_2") (pintype "passive"))
      (node (ref "D17") (pin "1") (pinfunction "CATHODE_1") (pintype "passive"))
      (node (ref "U75") (pin "11") (pinfunction "HB2_11") (pintype "passive"))
    )
    (net (code "23") (name "Net-(L8-Pad1)") (class "Default")
      (node (ref "L8") (pin "1") (pinfunction "1_1") (pintype "passive"))
      (node (ref "R357") (pin "2") (pinfunction "2_2") (pintype "passive"))
      (node (ref "R701") (pin "1") (pinfunction "1_1") (pintype "passive"))
    )
    (net (code "24") (name "Net-(L10-Pad2)") (class "Default")
      (node (ref "L10") (pin "2") (pinfunction "2_2") (pintype "passive"))
      (node (ref "R426") (pin "1") (pinfunction "1_1") (pintype "passive"))
      (node (ref "R703") (pin "1") (pinfunction "1_1") (pintype "passive"))
    )
    (net (code "25") (name "Net-(LD2-Pad2)") (class "Default")
      (node (ref "LD2") (pin "2") (pinfunction "2_2") (pintype "passive"))
      (node (ref "R1") (pin "2") (pinfunction "2_2") (pintype "passive"))
    )
    (net (code "26") (name "Net-(LD3-Pad2)") (class "Default")
      (node (ref "LD3") (pin "2") (pinfunction "2_2") (pintype "passive"))
      (node (ref "R3") (pin "2") (pinfunction "2_2") (pintype "passive"))
    )
    (net (code "27") (name "Net-(LD4-Pad2)") (class "Default")
      (node (ref "LD4") (pin "2") (pinfunction "2_2") (pintype "passive"))
      (node (ref "R2") (pin "2") (pinfunction "2_2") (pintype "passive"))
    )
    (net (code "28") (name "Net-(U14-VCC)") (class "Default")
      (node (ref "C51") (pin "1") (pinfunction "1_1") (pintype "passive"))
      (node (ref "U14") (pin "16") (pinfunction "VCC_16") (pintype "power_in"))
    )
    (net (code "29") (name "Net-(U71-D)") (class "Default")
      (node (ref "C320") (pin "2") (pinfunction "2_2") (pintype "passive"))
      (node (ref "L8") (pin "2") (pinfunction "2_2") (pintype "passive"))
      (node (ref "U71") (pin "5") (pinfunction "D_5") (pintype "passive"))
      (node (ref "U72") (pin "1") (pinfunction "S1_1") (pintype "passive"))
      (node (ref "U72") (pin "2") (pinfunction "S2_2") (pintype "passive"))
      (node (ref "U72") (pin "3") (pinfunction "S3_3") (pintype "passive"))
      (node (ref "U75") (pin "21") (pinfunction "SW1_21") (pintype "passive"))
    )
    (net (code "30") (name "Net-(U71-G)") (class "Default")
      (node (ref "R384") (pin "1") (pinfunction "1_1") (pintype "passive"))
      (node (ref "R387") (pin "1") (pinfunction "1_1") (pintype "passive"))
      (node (ref "U71") (pin "4") (pinfunction "G_4") (pintype "passive"))
    )
    (net (code "31") (name "Net-(U72-G)") (class "Default")
      (node (ref "R378") (pin "1") (pinfunction "1_1") (pintype "passive"))
      (node (ref "U72") (pin "4") (pinfunction "G_4") (pintype "passive"))
      (node (ref "U75") (pin "23") (pinfunction "HOL1_23") (pintype "passive"))
    )
    (net (code "32") (name "Net-(U75-CS1)") (class "Default")
      (node (ref "C683") (pin "2") (pinfunction "2_2") (pintype "passive"))
      (node (ref "R701") (pin "2") (pinfunction "2_2") (pintype "passive"))
      (node (ref "U75") (pin "27") (pinfunction "CS1_27") (pintype "passive"))
    )
    (net (code "33") (name "Net-(U75-CS2)") (class "Default")
      (node (ref "C684") (pin "1") (pinfunction "1_1") (pintype "passive"))
      (node (ref "R703") (pin "2") (pinfunction "2_2") (pintype "passive"))
      (node (ref "U75") (pin "4") (pinfunction "CS2_4") (pintype "passive"))
    )
    (net (code "34") (name "Net-(U75-HO1)") (class "Default")
      (node (ref "R378") (pin "2") (pinfunction "2_2") (pintype "passive"))
      (node (ref "U75") (pin "22") (pinfunction "HO1_22") (pintype "passive"))
    )
    (net (code "35") (name "Net-(U75-HO2)") (class "Default")
      (node (ref "R405") (pin "1") (pinfunction "1_1") (pintype "passive"))
      (node (ref "U75") (pin "9") (pinfunction "HO2_9") (pintype "passive"))
    )
    (net (code "36") (name "Net-(U75-HOL2)") (class "Default")
      (node (ref "R405") (pin "2") (pinfunction "2_2") (pintype "passive"))
      (node (ref "U75") (pin "8") (pinfunction "HOL2_8") (pintype "passive"))
      (node (ref "U78") (pin "4") (pinfunction "G_4") (pintype "passive"))
    )
    (net (code "37") (name "Net-(U75-LO1)") (class "Default")
      (node (ref "R387") (pin "2") (pinfunction "2_2") (pintype "passive"))
      (node (ref "U75") (pin "18") (pinfunction "LO1_18") (pintype "passive"))
    )
    (net (code "38") (name "Net-(U75-LO2)") (class "Default")
      (node (ref "R392") (pin "1") (pinfunction "1_1") (pintype "passive"))
      (node (ref "U75") (pin "13") (pinfunction "LO2_13") (pintype "passive"))
    )
    (net (code "39") (name "Net-(U75-LOL1)") (class "Default")
      (node (ref "R384") (pin "2") (pinfunction "2_2") (pintype "passive"))
      (node (ref "U75") (pin "19") (pinfunction "LOL1_19") (pintype "passive"))
    )
    (net (code "40") (name "Net-(U75-LOL2)") (class "Default")
      (node (ref "R396") (pin "1") (pinfunction "1_1") (pintype "passive"))
      (node (ref "U75") (pin "12") (pinfunction "LOL2_12") (pintype "passive"))
    )
    (net (code "41") (name "Net-(U75-RES)") (class "Default")
      (node (ref "C325") (pin "2") (pinfunction "2_2") (pintype "passive"))
      (node (ref "U75") (pin "32") (pinfunction "RES_32") (pintype "passive"))
    )
    (net (code "42") (name "Net-(U75-SS1)") (class "Default")
      (node (ref "C317") (pin "1") (pinfunction "1_1") (pintype "passive"))
      (node (ref "U75") (pin "30") (pinfunction "SS1_30") (pintype "passive"))
    )
    (net (code "43") (name "Net-(U75-SS2)") (class "Default")
      (node (ref "C345") (pin "1") (pinfunction "1_1") (pintype "passive"))
      (node (ref "U75") (pin "1") (pinfunction "SS2_1") (pintype "passive"))
    )
    (net (code "44") (name "Net-(U75-SW2)") (class "Default")
      (node (ref "C343") (pin "1") (pinfunction "1_1") (pintype "passive"))
      (node (ref "L10") (pin "1") (pinfunction "1_1") (pintype "passive"))
      (node (ref "U75") (pin "10") (pinfunction "SW2_10") (pintype "passive"))
      (node (ref "U78") (pin "1") (pinfunction "S1_1") (pintype "passive"))
      (node (ref "U78") (pin "2") (pinfunction "S2_2") (pintype "passive"))
      (node (ref "U78") (pin "3") (pinfunction "S3_3") (pintype "passive"))
      (node (ref "U81") (pin "5") (pinfunction "D_5") (pintype "passive"))
    )
    (net (code "45") (name "Net-(U75-VOUT1)") (class "Default")
      (node (ref "C683") (pin "1") (pinfunction "1_1") (pintype "passive"))
      (node (ref "R702") (pin "2") (pinfunction "2_2") (pintype "passive"))
      (node (ref "U75") (pin "26") (pinfunction "VOUT1_26") (pintype "power_in"))
    )
    (net (code "46") (name "Net-(U75-VOUT2)") (class "Default")
      (node (ref "C684") (pin "2") (pinfunction "2_2") (pintype "passive"))
      (node (ref "R704") (pin "2") (pinfunction "2_2") (pintype "passive"))
      (node (ref "U75") (pin "5") (pinfunction "VOUT2_5") (pintype "power_in"))
    )
    (net (code "47") (name "Net-(U81-G)") (class "Default")
      (node (ref "R392") (pin "2") (pinfunction "2_2") (pintype "passive"))
      (node (ref "R396") (pin "2") (pinfunction "2_2") (pintype "passive"))
      (node (ref "U81") (pin "4") (pinfunction "G_4") (pintype "passive"))
    )
    (net (code "48") (name "VCC3V3_PREREG") (class "Default")
      (node (ref "C283") (pin "1") (pinfunction "1_1") (pintype "passive"))
      (node (ref "C284") (pin "1") (pinfunction "1_1") (pintype "passive"))
      (node (ref "C290") (pin "1") (pinfunction "1_1") (pintype "passive"))
      (node (ref "R3") (pin "1") (pinfunction "1_1") (pintype "passive"))
      (node (ref "R357") (pin "1") (pinfunction "1_1") (pintype "passive"))
      (node (ref "R376") (pin "2") (pinfunction "2_2") (pintype "passive"))
      (node (ref "R702") (pin "1") (pinfunction "1_1") (pintype "passive"))
      (node (ref "TP1") (pin "1") (pinfunction "TP_1") (pintype "passive"))
    )
    (net (code "49") (name "VCC_5V0") (class "Default")
      (node (ref "C365") (pin "1") (pinfunction "1_1") (pintype "passive"))
      (node (ref "C367") (pin "1") (pinfunction "1_1") (pintype "passive"))
      (node (ref "C368") (pin "1") (pinfunction "1_1") (pintype "passive"))
      (node (ref "R1") (pin "1") (pinfunction "1_1") (pintype "passive"))
      (node (ref "R426") (pin "2") (pinfunction "2_2") (pintype "passive"))
      (node (ref "R704") (pin "1") (pinfunction "1_1") (pintype "passive"))
      (node (ref "TP7") (pin "1") (pinfunction "TP_1") (pintype "passive"))
      (node (ref "U75") (pin "6") (pinfunction "VCCX_6") (pintype "power_in"))
    )
    (net (code "50") (name "VCC_12V0") (class "Default")
      (node (ref "C10") (pin "1") (pinfunction "1_1") (pintype "passive"))
      (node (ref "C12") (pin "1") (pinfunction "1_1") (pintype "passive"))
      (node (ref "C24") (pin "1") (pinfunction "1_1") (pintype "passive"))
      (node (ref "C56") (pin "1") (pinfunction "1_1") (pintype "passive"))
      (node (ref "C7") (pin "1") (pinfunction "1_1") (pintype "passive"))
      (node (ref "C8") (pin "1") (pinfunction "1_1") (pintype "passive"))
      (node (ref "C9") (pin "1") (pinfunction "1_1") (pintype "passive"))
      (node (ref "D3") (pin "1") (pinfunction "CATHODE_1") (pintype "passive"))
      (node (ref "D5") (pin "1") (pinfunction "CATHODE_1") (pintype "passive"))
      (node (ref "R2") (pin "1") (pinfunction "1_1") (pintype "passive"))
      (node (ref "R54") (pin "1") (pinfunction "1_1") (pintype "passive"))
      (node (ref "TP66") (pin "1") (pinfunction "TP_1") (pintype "passive"))
      (node (ref "U14") (pin "10") (pinfunction "VOUT_10") (pintype "output"))
      (node (ref "U14") (pin "17") (pinfunction "VCCX_17") (pintype "power_in"))
    )
    (net (code "51") (name "VCC_LM5140") (class "Default")
      (node (ref "C330") (pin "1") (pinfunction "1_1") (pintype "passive"))
      (node (ref "C679") (pin "1") (pinfunction "1_1") (pintype "passive"))
      (node (ref "D15") (pin "2") (pinfunction "ANODE_2") (pintype "passive"))
      (node (ref "D17") (pin "2") (pinfunction "ANODE_2") (pintype "passive"))
      (node (ref "U75") (pin "15") (pinfunction "VCC_15") (pintype "power_in"))
      (node (ref "U75") (pin "16") (pinfunction "VCC_16") (pintype "power_in"))
    )
    (net (code "52") (name "VDDA_LM5140") (class "Default")
      (node (ref "C318") (pin "1") (pinfunction "1_1") (pintype "passive"))
      (node (ref "R404") (pin "2") (pinfunction "2_2") (pintype "passive"))
      (node (ref "U75") (pin "28") (pinfunction "FB1_28") (pintype "passive"))
      (node (ref "U75") (pin "3") (pinfunction "FB2_3") (pintype "passive"))
      (node (ref "U75") (pin "33") (pinfunction "DEMB_33") (pintype "passive"))
      (node (ref "U75") (pin "34") (pinfunction "ILSET_34") (pintype "passive"))
      (node (ref "U75") (pin "36") (pinfunction "VDDA_36") (pintype "power_in"))
      (node (ref "U75") (pin "37") (pinfunction "OSC_37") (pintype "passive"))
    )
    (net (code "53") (name "VMAIN") (class "Default")
      (node (ref "C340") (pin "1") (pinfunction "1_1") (pintype "passive"))
      (node (ref "C68") (pin "1") (pinfunction "1_1") (pintype "passive"))
      (node (ref "C680") (pin "1") (pinfunction "1_1") (pintype "passive"))
      (node (ref "C681") (pin "1") (pinfunction "1_1") (pintype "passive"))
      (node (ref "C69") (pin "1") (pinfunction "1_1") (pintype "passive"))
      (node (ref "R68") (pin "1") (pinfunction "1_1") (pintype "passive"))
      (node (ref "U14") (pin "1") (pinfunction "VIN_1") (pintype "input"))
      (node (ref "U14") (pin "4") (pinfunction "EN_4") (pintype "passive"))
      (node (ref "U18") (pin "5") (pinfunction "D1_5") (pintype "passive"))
      (node (ref "U18") (pin "6") (pinfunction "D2_6") (pintype "passive"))
      (node (ref "U18") (pin "7") (pinfunction "D3_7") (pintype "passive"))
      (node (ref "U18") (pin "8") (pinfunction "D4_8") (pintype "passive"))
      (node (ref "U72") (pin "5") (pinfunction "D_5") (pintype "passive"))
      (node (ref "U75") (pin "25") (pinfunction "VIN_25") (pintype "input"))
      (node (ref "U75") (pin "31") (pinfunction "EN1_31") (pintype "passive"))
      (node (ref "U75") (pin "40") (pinfunction "EN2_40") (pintype "passive"))
      (node (ref "U78") (pin "5") (pinfunction "D_5") (pintype "passive"))
    )
    (net (code "54") (name "unconnected-(U14-SYNC-Pad11)") (class "Default")
      (node (ref "U14") (pin "11") (pinfunction "SYNC_11") (pintype "passive+no_connect"))
    )
    (net (code "55") (name "unconnected-(U75-SYNOUT-Pad39)") (class "Default")
      (node (ref "U75") (pin "39") (pinfunction "SYNOUT_39") (pintype "output+no_connect"))
    )
  )
)
